# oring_circuit.net
KiCad netlist of a schematic drawn in Altium Designer
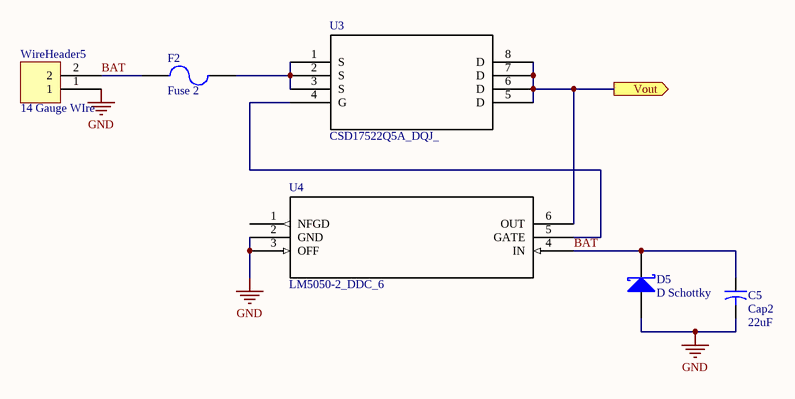
[diagram p0: oring_circuit.SchDoc]

(export (version "E")
  (design (tool "Eeschema 10.0.6"))
  (components
    (comp (ref "C5")
      (value "Cap2")
      (footprint "CAPR5-4X5")
      (description "Capacitor")
      (fields (field (name "ALTIUM_VALUE") "22uF") (field (name "PUBLISHER") "Altium Limited"))
      (libsource (lib "Miscellaneous Devices") (part "Cap2"))
    )
    (comp (ref "D5")
      (value "D Schottky")
      (footprint "DIODE")
      (description "Schottky Diode")
      (fields (field (name "PUBLISHER") "Altium Limited"))
      (libsource (lib "Miscellaneous Devices") (part "D Schottky"))
    )
    (comp (ref "F2")
      (value "Fuse 2")
      (footprint "FUSE")
      (description "Fuse")
      (fields (field (name "PUBLISHER") "Altium Limited"))
      (libsource (lib "Miscellaneous Devices") (part "Fuse 2"))
    )
    (comp (ref "U3")
      (value "CSD17522Q5A_DQJ_")
      (footprint "DQJ8")
      (description "Imported")
      (fields
        (field (name "MANUFACTURER") "Texas Instruments")
        (field (name "GENERIC_PART_NUMBER") "CSD17522Q5A")
      )
      (libsource (lib "CSD17522Q5A") (part "CSD17522Q5A_DQJ_"))
    )
    (comp (ref "U4")
      (value "LM5050-2_DDC_6")
      (footprint "MK06A")
      (description "Imported")
      (fields
        (field (name "MANUFACTURER") "Texas Instruments")
        (field (name "MANUFACTURER_PART_NUMBER") "lm5050-2_ddc_6")
      )
      (libsource (lib "lm5050-2") (part "LM5050-2_DDC_6"))
    )
    (comp (ref "WireHeader5")
      (value "14 Gauge WIre")
      (footprint "WireHeader")
      (libsource (lib "InvestiGator") (part "WireHeader"))
    )
  )
  (nets
    (net (code "2") (name "/BAT") (class "Default")
      (node (ref "C5") (pin "1") (pinfunction "1_1") (pintype "passive"))
      (node (ref "D5") (pin "2") (pinfunction "K_2") (pintype "passive"))
      (node (ref "F2") (pin "1") (pinfunction "1_1") (pintype "passive"))
      (node (ref "U4") (pin "4") (pinfunction "IN_4") (pintype "input"))
      (node (ref "WireHeader5") (pin "2") (pinfunction "2_2") (pintype "passive"))
    )
    (net (code "3") (name "/Vout") (class "Default")
      (node (ref "U3") (pin "5") (pinfunction "D_5") (pintype "passive"))
      (node (ref "U3") (pin "6") (pinfunction "D_6") (pintype "passive"))
      (node (ref "U3") (pin "7") (pinfunction "D_7") (pintype "passive"))
      (node (ref "U3") (pin "8") (pinfunction "D_8") (pintype "passive"))
      (node (ref "U4") (pin "6") (pinfunction "OUT_6") (pintype "passive"))
    )
    (net (code "4") (name "GND") (class "Default")
      (node (ref "C5") (pin "2") (pinfunction "2_2") (pintype "passive"))
      (node (ref "D5") (pin "1") (pinfunction "A_1") (pintype "passive"))
      (node (ref "U4") (pin "2") (pinfunction "GND_2") (pintype "power_in"))
      (node (ref "U4") (pin "3") (pinfunction "OFF_3") (pintype "input"))
      (node (ref "WireHeader5") (pin "1") (pinfunction "1_1") (pintype "passive"))
    )
    (net (code "5") (name "Net-(F2-Pad2)") (class "Default")
      (node (ref "F2") (pin "2") (pinfunction "2_2") (pintype "passive"))
      (node (ref "U3") (pin "1") (pinfunction "S_1") (pintype "passive"))
      (node (ref "U3") (pin "2") (pinfunction "S_2") (pintype "passive"))
      (node (ref "U3") (pin "3") (pinfunction "S_3") (pintype "passive"))
    )
    (net (code "6") (name "Net-(U3-G)") (class "Default")
      (node (ref "U3") (pin "4") (pinfunction "G_4") (pintype "passive"))
      (node (ref "U4") (pin "5") (pinfunction "GATE_5") (pintype "passive"))
    )
    (net (code "7") (name "unconnected-(U4-NFGD-Pad1)") (class "Default")
      (node (ref "U4") (pin "1") (pinfunction "NFGD_1") (pintype "output"))
    )
  )
)
